# GIP-gps.net
KiCad netlist of a schematic drawn in EAGLE
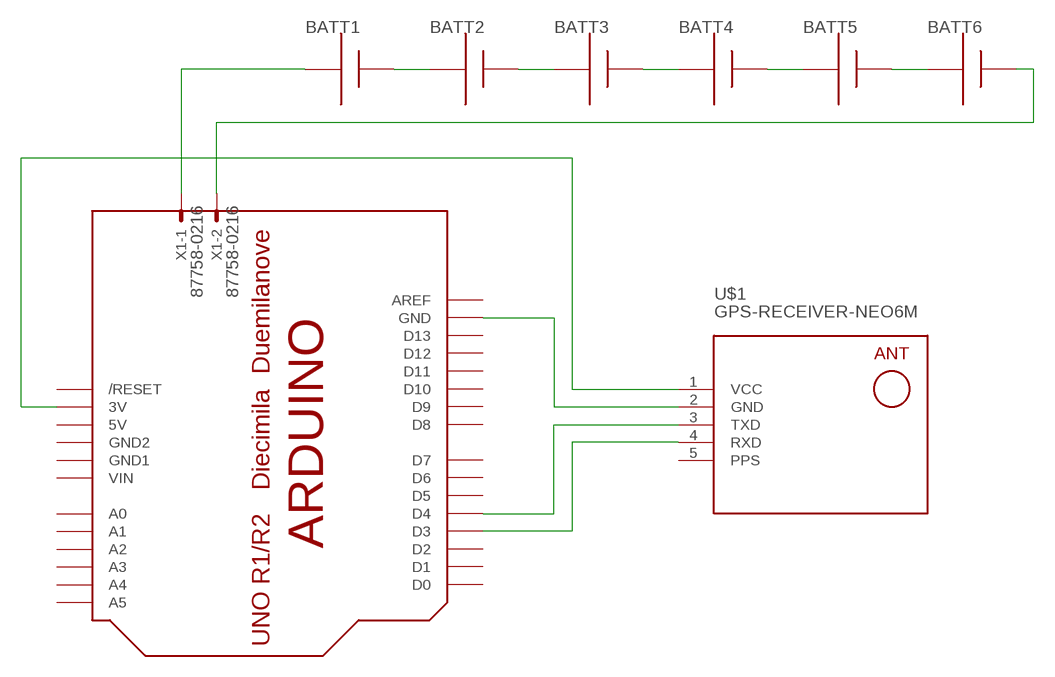
[diagram p0: schematic, sheet 1]

(export (version "E")
  (design (tool "Eeschema 10.0.6"))
  (components
    (comp (ref "BATT1")
      (value "AAA")
      (footprint "eagle-import:12BH412")
      (libsource (lib "eagle-import") (part "AAA"))
    )
    (comp (ref "BATT2")
      (value "AAA")
      (footprint "eagle-import:12BH412")
      (libsource (lib "eagle-import") (part "AAA"))
    )
    (comp (ref "BATT3")
      (value "AAA")
      (footprint "eagle-import:12BH412")
      (libsource (lib "eagle-import") (part "AAA"))
    )
    (comp (ref "BATT4")
      (value "AAA")
      (footprint "eagle-import:12BH412")
      (libsource (lib "eagle-import") (part "AAA"))
    )
    (comp (ref "BATT5")
      (value "AAA")
      (footprint "eagle-import:12BH412")
      (libsource (lib "eagle-import") (part "AAA"))
    )
    (comp (ref "BATT6")
      (value "AAA")
      (footprint "eagle-import:12BH412")
      (libsource (lib "eagle-import") (part "AAA"))
    )
    (comp (ref "U$1")
      (value "GPS-RECEIVER-NEO6M")
      (footprint "eagle-import:GPS-RECEIVER-NEO6M")
      (libsource (lib "eagle-import") (part "GPS-RECEIVER-NEO6M"))
    )
    (comp (ref "U$2")
      (value "ARDUINO-BPLACE")
      (footprint "eagle-import:ARDUINO-BPLACE")
      (libsource (lib "eagle-import") (part "ARDUINO-BPLACE"))
    )
    (comp (ref "X1")
      (value "87758-0216")
      (footprint "eagle-import:87758-0216")
      (fields (field (name "MF") "MOLEX"))
      (libsource (lib "eagle-import") (part "87758-0216"))
    )
  )
  (nets
    (net (code "1") (name "/5V") (class "Default")
      (node (ref "U$2") (pin "5V") (pinfunction "5V_5V") (pintype "power_in"))
    )
    (net (code "2") (name "/GND1") (class "Default")
      (node (ref "U$2") (pin "GND1") (pinfunction "GND1_GND1") (pintype "power_in"))
    )
    (net (code "3") (name "/GND2") (class "Default")
      (node (ref "U$2") (pin "GND2") (pinfunction "GND2_GND2") (pintype "power_in"))
    )
    (net (code "4") (name "/PPS") (class "Default")
      (node (ref "U$1") (pin "5") (pinfunction "PPS_5") (pintype "power_in"))
    )
    (net (code "5") (name "/VIN") (class "Default")
      (node (ref "U$2") (pin "VIN") (pinfunction "VIN_VIN") (pintype "power_in"))
    )
    (net (code "6") (name "Net-(BATT1-Pad+)") (class "Default")
      (node (ref "BATT1") (pin "+") (pinfunction "+_+") (pintype "bidirectional"))
      (node (ref "BATT2") (pin "-") (pinfunction "-_-") (pintype "bidirectional"))
    )
    (net (code "7") (name "Net-(BATT2-Pad+)") (class "Default")
      (node (ref "BATT2") (pin "+") (pinfunction "+_+") (pintype "bidirectional"))
      (node (ref "BATT3") (pin "-") (pinfunction "-_-") (pintype "bidirectional"))
    )
    (net (code "8") (name "Net-(BATT3-Pad+)") (class "Default")
      (node (ref "BATT3") (pin "+") (pinfunction "+_+") (pintype "bidirectional"))
      (node (ref "BATT4") (pin "-") (pinfunction "-_-") (pintype "bidirectional"))
    )
    (net (code "9") (name "Net-(BATT4-Pad+)") (class "Default")
      (node (ref "BATT4") (pin "+") (pinfunction "+_+") (pintype "bidirectional"))
      (node (ref "BATT5") (pin "-") (pinfunction "-_-") (pintype "bidirectional"))
    )
    (net (code "10") (name "Net-(BATT5-Pad+)") (class "Default")
      (node (ref "BATT5") (pin "+") (pinfunction "+_+") (pintype "bidirectional"))
      (node (ref "BATT6") (pin "-") (pinfunction "-_-") (pintype "bidirectional"))
    )
    (net (code "11") (name "Net-(U$1-GND)") (class "Default")
      (node (ref "U$1") (pin "2") (pinfunction "GND_2") (pintype "bidirectional"))
      (node (ref "U$2") (pin "GND") (pinfunction "GND_GND") (pintype "power_in"))
    )
    (net (code "12") (name "Net-(U$1-RXD)") (class "Default")
      (node (ref "U$1") (pin "4") (pinfunction "RXD_4") (pintype "power_in"))
      (node (ref "U$2") (pin "D3") (pinfunction "D3_D3") (pintype "bidirectional"))
    )
    (net (code "13") (name "Net-(U$1-TXD)") (class "Default")
      (node (ref "U$1") (pin "3") (pinfunction "TXD_3") (pintype "bidirectional"))
      (node (ref "U$2") (pin "D4") (pinfunction "D4_D4") (pintype "bidirectional"))
    )
    (net (code "14") (name "Net-(U$1-VCC)") (class "Default")
      (node (ref "U$1") (pin "1") (pinfunction "VCC_1") (pintype "bidirectional"))
      (node (ref "U$2") (pin "3V") (pinfunction "3V_3V") (pintype "power_in"))
    )
    (net (code "15") (name "Net-(X1A-S)") (class "Default")
      (node (ref "BATT1") (pin "-") (pinfunction "-_-") (pintype "bidirectional"))
      (node (ref "X1") (pin "1") (pinfunction "S_1") (pintype "passive"))
    )
    (net (code "16") (name "Net-(X1B-S)") (class "Default")
      (node (ref "BATT6") (pin "+") (pinfunction "+_+") (pintype "bidirectional"))
      (node (ref "X1") (pin "2") (pinfunction "S_2") (pintype "passive"))
    )
    (net (code "17") (name "unconnected-(U$2-PadA0)") (class "Default")
      (node (ref "U$2") (pin "A0") (pinfunction "A0_A0") (pintype "bidirectional"))
    )
    (net (code "18") (name "unconnected-(U$2-PadA1)") (class "Default")
      (node (ref "U$2") (pin "A1") (pinfunction "A1_A1") (pintype "bidirectional"))
    )
    (net (code "19") (name "unconnected-(U$2-PadA2)") (class "Default")
      (node (ref "U$2") (pin "A2") (pinfunction "A2_A2") (pintype "bidirectional"))
    )
    (net (code "20") (name "unconnected-(U$2-PadA3)") (class "Default")
      (node (ref "U$2") (pin "A3") (pinfunction "A3_A3") (pintype "bidirectional"))
    )
    (net (code "21") (name "unconnected-(U$2-PadA4)") (class "Default")
      (node (ref "U$2") (pin "A4") (pinfunction "A4_A4") (pintype "bidirectional"))
    )
    (net (code "22") (name "unconnected-(U$2-PadA5)") (class "Default")
      (node (ref "U$2") (pin "A5") (pinfunction "A5_A5") (pintype "bidirectional"))
    )
    (net (code "23") (name "unconnected-(U$2-PadAREF)") (class "Default")
      (node (ref "U$2") (pin "AREF") (pinfunction "AREF_AREF") (pintype "bidirectional"))
    )
    (net (code "24") (name "unconnected-(U$2-PadD0)") (class "Default")
      (node (ref "U$2") (pin "D0") (pinfunction "D0_D0") (pintype "bidirectional"))
    )
    (net (code "25") (name "unconnected-(U$2-PadD1)") (class "Default")
      (node (ref "U$2") (pin "D1") (pinfunction "D1_D1") (pintype "bidirectional"))
    )
    (net (code "26") (name "unconnected-(U$2-PadD2)") (class "Default")
      (node (ref "U$2") (pin "D2") (pinfunction "D2_D2") (pintype "bidirectional"))
    )
    (net (code "27") (name "unconnected-(U$2-PadD5)") (class "Default")
      (node (ref "U$2") (pin "D5") (pinfunction "D5_D5") (pintype "bidirectional"))
    )
    (net (code "28") (name "unconnected-(U$2-PadD6)") (class "Default")
      (node (ref "U$2") (pin "D6") (pinfunction "D6_D6") (pintype "bidirectional"))
    )
    (net (code "29") (name "unconnected-(U$2-PadD7)") (class "Default")
      (node (ref "U$2") (pin "D7") (pinfunction "D7_D7") (pintype "bidirectional"))
    )
    (net (code "30") (name "unconnected-(U$2-PadD8)") (class "Default")
      (node (ref "U$2") (pin "D8") (pinfunction "D8_D8") (pintype "bidirectional"))
    )
    (net (code "31") (name "unconnected-(U$2-PadD9)") (class "Default")
      (node (ref "U$2") (pin "D9") (pinfunction "D9_D9") (pintype "bidirectional"))
    )
    (net (code "32") (name "unconnected-(U$2-PadD10)") (class "Default")
      (node (ref "U$2") (pin "D10") (pinfunction "D10_D10") (pintype "bidirectional"))
    )
    (net (code "33") (name "unconnected-(U$2-PadD11)") (class "Default")
      (node (ref "U$2") (pin "D11") (pinfunction "D11_D11") (pintype "bidirectional"))
    )
    (net (code "34") (name "unconnected-(U$2-PadD12)") (class "Default")
      (node (ref "U$2") (pin "D12") (pinfunction "D12_D12") (pintype "bidirectional"))
    )
    (net (code "35") (name "unconnected-(U$2-PadD13)") (class "Default")
      (node (ref "U$2") (pin "D13") (pinfunction "D13_D13") (pintype "bidirectional"))
    )
    (net (code "36") (name "unconnected-(U$2-{slash}RESET-PadRESET)") (class "Default")
      (node (ref "U$2") (pin "RESET") (pinfunction "/RESET_RESET") (pintype "bidirectional"))
    )
  )
)
